# attiny84breakout.net
KiCad netlist of a schematic drawn in EAGLE
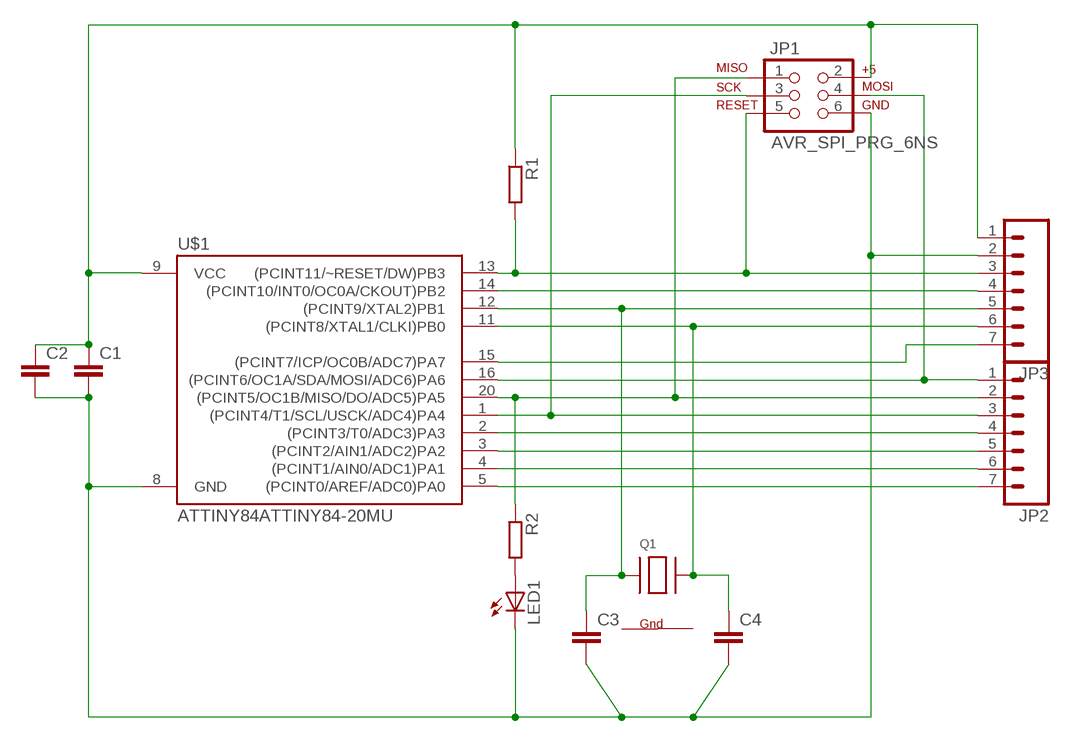
[diagram p0: schematic, sheet 1]

(export (version "E")
  (design (tool "Eeschema 10.0.6"))
  (components
    (comp (ref "C1")
      (value "C-EUC0402")
      (footprint "eagle-import:C0402")
      (libsource (lib "eagle-import") (part "C-EUC0402"))
    )
    (comp (ref "C2")
      (value "C-EUC0402")
      (footprint "eagle-import:C0402")
      (libsource (lib "eagle-import") (part "C-EUC0402"))
    )
    (comp (ref "C3")
      (value "C-EUC0402")
      (footprint "eagle-import:C0402")
      (libsource (lib "eagle-import") (part "C-EUC0402"))
    )
    (comp (ref "C4")
      (value "C-EUC0402")
      (footprint "eagle-import:C0402")
      (libsource (lib "eagle-import") (part "C-EUC0402"))
    )
    (comp (ref "JP1")
      (value "AVR_SPI_PRG_6NS")
      (footprint "eagle-import:2X3-NS")
      (libsource (lib "eagle-import") (part "AVR_SPI_PRG_6NS"))
    )
    (comp (ref "JP2")
      (value "M07")
      (footprint "eagle-import:1X07")
      (libsource (lib "eagle-import") (part "M07"))
    )
    (comp (ref "JP3")
      (value "M07")
      (footprint "eagle-import:1X07")
      (libsource (lib "eagle-import") (part "M07"))
    )
    (comp (ref "LED1")
      (value "LEDCHIP-LED0805")
      (footprint "eagle-import:CHIP-LED0805")
      (libsource (lib "eagle-import") (part "LEDCHIP-LED0805"))
    )
    (comp (ref "Q1")
      (value "XTAL-4-3225")
      (footprint "eagle-import:NX3225")
      (libsource (lib "eagle-import") (part "XTAL-4-3225"))
    )
    (comp (ref "R1")
      (value "R-EU_R0603")
      (footprint "eagle-import:R0603")
      (libsource (lib "eagle-import") (part "R-EU_R0603"))
    )
    (comp (ref "R2")
      (value "R-EU_R0603")
      (footprint "eagle-import:R0603")
      (libsource (lib "eagle-import") (part "R-EU_R0603"))
    )
    (comp (ref "U$1")
      (value "ATTINY84ATTINY84-20MU")
      (footprint "eagle-import:QFN20")
      (libsource (lib "eagle-import") (part "ATTINY84ATTINY84-20MU"))
    )
  )
  (nets
    (net (code "1") (name "/G1") (class "Default")
      (node (ref "Q1") (pin "4") (pinfunction "G1_4") (pintype "power_in"))
    )
    (net (code "2") (name "/G2") (class "Default")
      (node (ref "Q1") (pin "2") (pinfunction "G2_2") (pintype "power_in"))
    )
    (net (code "3") (name "Net-(LED1-PadA)") (class "Default")
      (node (ref "LED1") (pin "A") (pinfunction "A_A") (pintype "passive"))
      (node (ref "R2") (pin "2") (pinfunction "2_2") (pintype "passive"))
    )
    (net (code "4") (name "Net-(Q1-X1)") (class "Default")
      (node (ref "C3") (pin "1") (pinfunction "1_1") (pintype "passive"))
      (node (ref "JP3") (pin "5") (pinfunction "5_5") (pintype "passive"))
      (node (ref "Q1") (pin "1") (pinfunction "X1_1") (pintype "bidirectional"))
      (node (ref "U$1") (pin "12") (pinfunction "(PCINT9/XTAL2)PB1_12") (pintype "bidirectional"))
    )
    (net (code "5") (name "Net-(Q1-X2)") (class "Default")
      (node (ref "C4") (pin "1") (pinfunction "1_1") (pintype "passive"))
      (node (ref "JP3") (pin "6") (pinfunction "6_6") (pintype "passive"))
      (node (ref "Q1") (pin "3") (pinfunction "X2_3") (pintype "bidirectional"))
      (node (ref "U$1") (pin "11") (pinfunction "(PCINT8/XTAL1/CLKI)PB0_11") (pintype "bidirectional"))
    )
    (net (code "6") (name "Net-(U$1-(PCINT0{slash}AREF{slash}ADC0)PA0)") (class "Default")
      (node (ref "JP2") (pin "7") (pinfunction "7_7") (pintype "passive"))
      (node (ref "U$1") (pin "5") (pinfunction "(PCINT0/AREF/ADC0)PA0_5") (pintype "bidirectional"))
    )
    (net (code "7") (name "Net-(U$1-(PCINT1{slash}AIN0{slash}ADC1)PA1)") (class "Default")
      (node (ref "JP2") (pin "6") (pinfunction "6_6") (pintype "passive"))
      (node (ref "U$1") (pin "4") (pinfunction "(PCINT1/AIN0/ADC1)PA1_4") (pintype "bidirectional"))
    )
    (net (code "8") (name "Net-(U$1-(PCINT2{slash}AIN1{slash}ADC2)PA2)") (class "Default")
      (node (ref "JP2") (pin "5") (pinfunction "5_5") (pintype "passive"))
      (node (ref "U$1") (pin "3") (pinfunction "(PCINT2/AIN1/ADC2)PA2_3") (pintype "bidirectional"))
    )
    (net (code "9") (name "Net-(U$1-(PCINT3{slash}T0{slash}ADC3)PA3)") (class "Default")
      (node (ref "JP2") (pin "4") (pinfunction "4_4") (pintype "passive"))
      (node (ref "U$1") (pin "2") (pinfunction "(PCINT3/T0/ADC3)PA3_2") (pintype "bidirectional"))
    )
    (net (code "10") (name "Net-(U$1-(PCINT4{slash}T1{slash}SCL{slash}USCK{slash}ADC4)PA4)") (class "Default")
      (node (ref "JP1") (pin "3") (pinfunction "3_3") (pintype "passive"))
      (node (ref "JP2") (pin "3") (pinfunction "3_3") (pintype "passive"))
      (node (ref "U$1") (pin "1") (pinfunction "(PCINT4/T1/SCL/USCK/ADC4)PA4_1") (pintype "bidirectional"))
    )
    (net (code "11") (name "Net-(U$1-(PCINT5{slash}OC1B{slash}MISO{slash}DO{slash}ADC5)PA5)") (class "Default")
      (node (ref "JP1") (pin "1") (pinfunction "1_1") (pintype "passive"))
      (node (ref "JP2") (pin "2") (pinfunction "2_2") (pintype "passive"))
      (node (ref "R2") (pin "1") (pinfunction "1_1") (pintype "passive"))
      (node (ref "U$1") (pin "20") (pinfunction "(PCINT5/OC1B/MISO/DO/ADC5)PA5_20") (pintype "bidirectional"))
    )
    (net (code "12") (name "Net-(U$1-(PCINT6{slash}OC1A{slash}SDA{slash}MOSI{slash}ADC6)PA6)") (class "Default")
      (node (ref "JP1") (pin "4") (pinfunction "4_4") (pintype "passive"))
      (node (ref "JP2") (pin "1") (pinfunction "1_1") (pintype "passive"))
      (node (ref "U$1") (pin "16") (pinfunction "(PCINT6/OC1A/SDA/MOSI/ADC6)PA6_16") (pintype "bidirectional"))
    )
    (net (code "13") (name "Net-(U$1-(PCINT7{slash}ICP{slash}OC0B{slash}ADC7)PA7)") (class "Default")
      (node (ref "JP3") (pin "7") (pinfunction "7_7") (pintype "passive"))
      (node (ref "U$1") (pin "15") (pinfunction "(PCINT7/ICP/OC0B/ADC7)PA7_15") (pintype "bidirectional"))
    )
    (net (code "14") (name "Net-(U$1-(PCINT10{slash}INT0{slash}OC0A{slash}CKOUT)PB2)") (class "Default")
      (node (ref "JP3") (pin "4") (pinfunction "4_4") (pintype "passive"))
      (node (ref "U$1") (pin "14") (pinfunction "(PCINT10/INT0/OC0A/CKOUT)PB2_14") (pintype "bidirectional"))
    )
    (net (code "15") (name "Net-(U$1-(PCINT11{slash}~{RESET{slash}DW})PB3)") (class "Default")
      (node (ref "JP1") (pin "5") (pinfunction "5_5") (pintype "passive"))
      (node (ref "JP3") (pin "3") (pinfunction "3_3") (pintype "passive"))
      (node (ref "R1") (pin "2") (pinfunction "2_2") (pintype "passive"))
      (node (ref "U$1") (pin "13") (pinfunction "(PCINT11/~{RESET/DW})PB3_13") (pintype "bidirectional"))
    )
    (net (code "16") (name "Net-(U$1-GND)") (class "Default")
      (node (ref "C1") (pin "2") (pinfunction "2_2") (pintype "passive"))
      (node (ref "C2") (pin "2") (pinfunction "2_2") (pintype "passive"))
      (node (ref "C3") (pin "2") (pinfunction "2_2") (pintype "passive"))
      (node (ref "C4") (pin "2") (pinfunction "2_2") (pintype "passive"))
      (node (ref "JP1") (pin "6") (pinfunction "6_6") (pintype "passive"))
      (node (ref "JP3") (pin "2") (pinfunction "2_2") (pintype "passive"))
      (node (ref "LED1") (pin "C") (pinfunction "C_C") (pintype "passive"))
      (node (ref "U$1") (pin "8") (pinfunction "GND_8") (pintype "bidirectional"))
    )
    (net (code "17") (name "Net-(U$1-VCC)") (class "Default")
      (node (ref "C1") (pin "1") (pinfunction "1_1") (pintype "passive"))
      (node (ref "C2") (pin "1") (pinfunction "1_1") (pintype "passive"))
      (node (ref "JP1") (pin "2") (pinfunction "2_2") (pintype "passive"))
      (node (ref "JP3") (pin "1") (pinfunction "1_1") (pintype "passive"))
      (node (ref "R1") (pin "1") (pinfunction "1_1") (pintype "passive"))
      (node (ref "U$1") (pin "9") (pinfunction "VCC_9") (pintype "bidirectional"))
    )
  )
)
